# cpuConnectionBoard.net
KiCad netlist of a schematic drawn in EAGLE
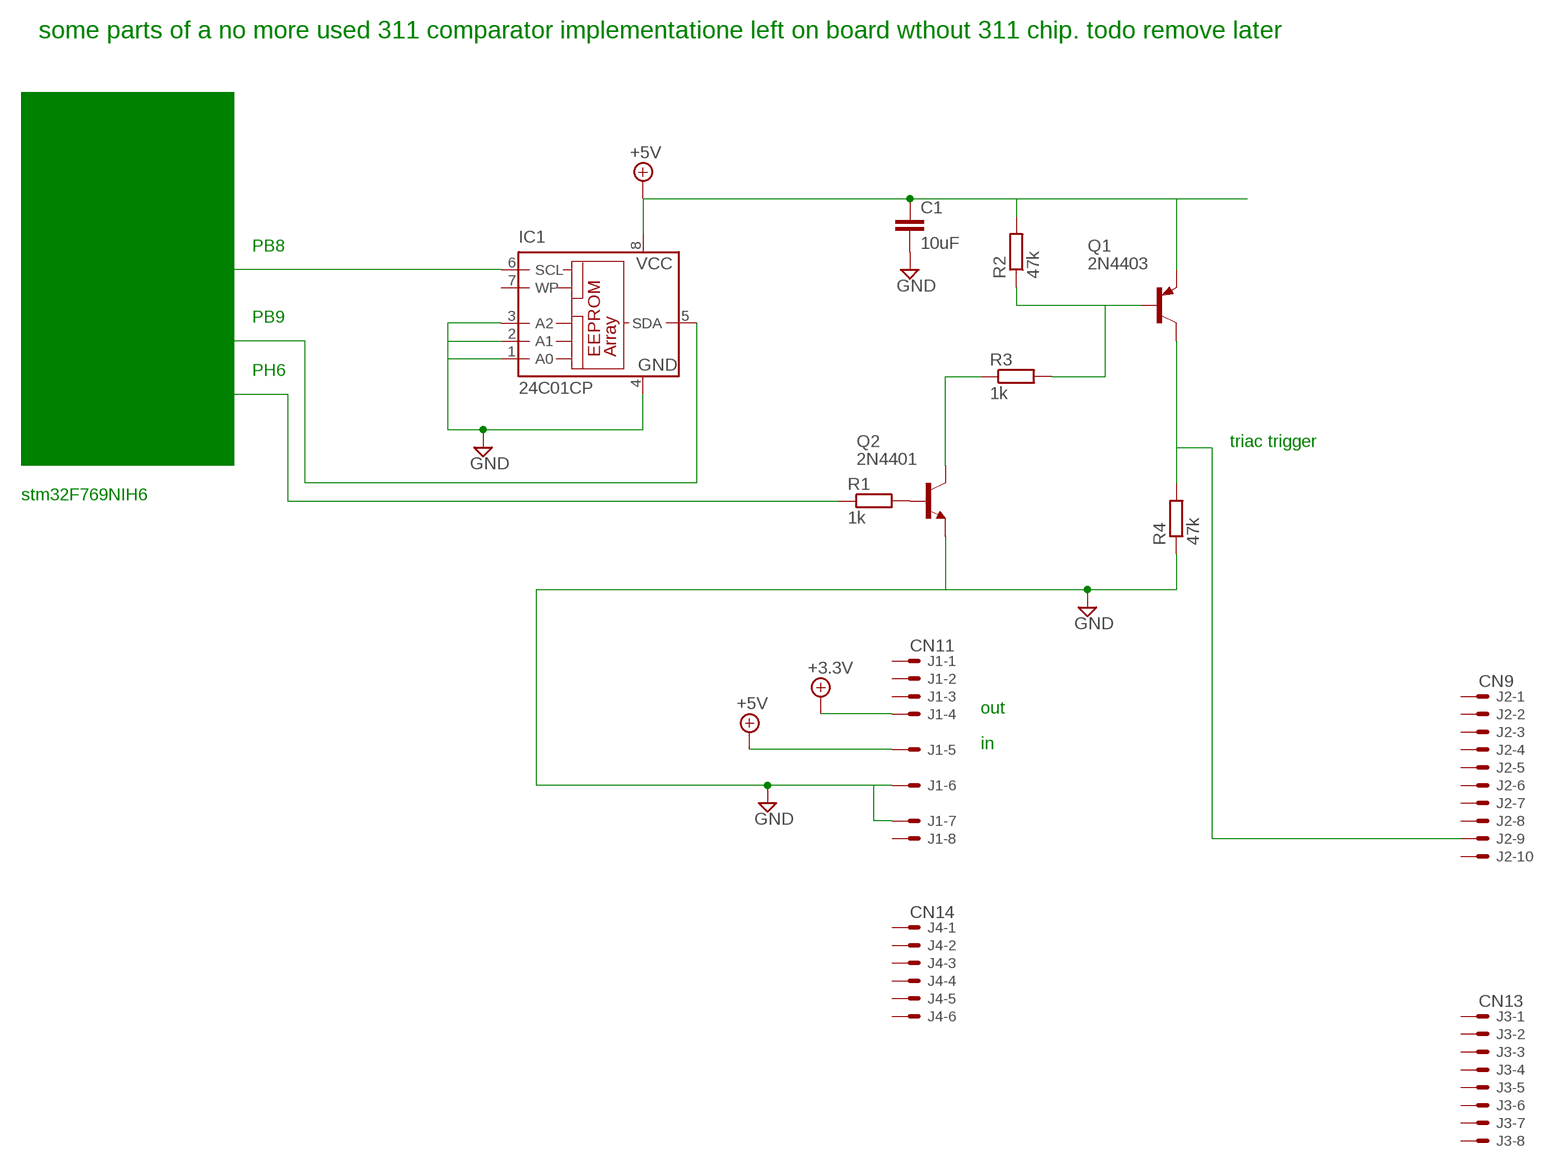
[diagram p0: schematic, sheet 1]

(export (version "E")
  (design (tool "Eeschema 10.0.6"))
  (components
    (comp (ref "C1")
      (value "10uF")
      (footprint "eagle-import:C050-030X075")
      (libsource (lib "eagle-import") (part "C-EU050-030X075"))
    )
    (comp (ref "IC1")
      (value "24C01CP")
      (footprint "eagle-import:DIL8")
      (fields (field (name "MF") "MICROCHIP") (field (name "MPN") "24C01C/P"))
      (libsource (lib "eagle-import") (part "24CP01C"))
    )
    (comp (ref "J1")
      (value "CN11")
      (footprint "eagle-import:XF2E-0815-1")
      (fields (field (name "MPN") "XF2E-0815-1"))
      (libsource (lib "eagle-import") (part "XF2-08?15-1E"))
    )
    (comp (ref "J2")
      (value "CN9")
      (footprint "eagle-import:XF2E-1015-1")
      (fields (field (name "MPN") "XF2E-1015-1"))
      (libsource (lib "eagle-import") (part "XF2-10?15-1E"))
    )
    (comp (ref "J3")
      (value "CN13")
      (footprint "eagle-import:XF2E-0815-1")
      (fields (field (name "MPN") "XF2E-0815-1"))
      (libsource (lib "eagle-import") (part "XF2-08?15-1E"))
    )
    (comp (ref "J4")
      (value "CN14")
      (footprint "eagle-import:XF2E-0815-1")
      (fields (field (name "MPN") "XF2E-0815-1"))
      (libsource (lib "eagle-import") (part "XF2-08?15-1E"))
    )
    (comp (ref "Q1")
      (value "2N4403")
      (footprint "eagle-import:TO3")
      (libsource (lib "eagle-import") (part "2N4902"))
    )
    (comp (ref "Q2")
      (value "2N4401")
      (footprint "eagle-import:TO92")
      (libsource (lib "eagle-import") (part "2N4416"))
    )
    (comp (ref "R1")
      (value "1k")
      (footprint "eagle-import:0309_12")
      (libsource (lib "eagle-import") (part "R-EU_0309/12"))
    )
    (comp (ref "R2")
      (value "47k")
      (footprint "eagle-import:0309_12")
      (libsource (lib "eagle-import") (part "R-EU_0309/12"))
    )
    (comp (ref "R3")
      (value "1k")
      (footprint "eagle-import:0309_12")
      (libsource (lib "eagle-import") (part "R-EU_0309/12"))
    )
    (comp (ref "R4")
      (value "47k")
      (footprint "eagle-import:0309_12")
      (libsource (lib "eagle-import") (part "R-EU_0309/12"))
    )
  )
  (nets
    (net (code "1") (name "+3.3V") (class "Default")
      (node (ref "C1") (pin "1") (pinfunction "1_1") (pintype "passive"))
      (node (ref "IC1") (pin "8") (pinfunction "VCC_8") (pintype "power_in"))
      (node (ref "J1") (pin "4") (pinfunction "MS_4") (pintype "passive"))
      (node (ref "J1") (pin "5") (pinfunction "MS_5") (pintype "passive"))
      (node (ref "Q1") (pin "E") (pinfunction "E_E") (pintype "passive"))
      (node (ref "R2") (pin "2") (pinfunction "2_2") (pintype "passive"))
    )
    (net (code "2") (name "GND") (class "Default")
      (node (ref "C1") (pin "2") (pinfunction "2_2") (pintype "passive"))
      (node (ref "IC1") (pin "1") (pinfunction "A0_1") (pintype "input"))
      (node (ref "IC1") (pin "2") (pinfunction "A1_2") (pintype "input"))
      (node (ref "IC1") (pin "3") (pinfunction "A2_3") (pintype "input"))
      (node (ref "IC1") (pin "4") (pinfunction "GND_4") (pintype "power_in"))
      (node (ref "J1") (pin "6") (pinfunction "MS_6") (pintype "passive"))
      (node (ref "J1") (pin "7") (pinfunction "MS_7") (pintype "passive"))
      (node (ref "Q2") (pin "3") (pinfunction "E_3") (pintype "passive"))
      (node (ref "R4") (pin "1") (pinfunction "1_1") (pintype "passive"))
    )
    (net (code "3") (name "Net-(J2J-MS)") (class "Default")
      (node (ref "J2") (pin "9") (pinfunction "MS_9") (pintype "passive"))
      (node (ref "Q1") (pin "C") (pinfunction "C_C") (pintype "passive"))
      (node (ref "Q1") (pin "C/") (pinfunction "C_C/") (pintype "passive"))
      (node (ref "R4") (pin "2") (pinfunction "2_2") (pintype "passive"))
    )
    (net (code "4") (name "Net-(Q1-PadB)") (class "Default")
      (node (ref "Q1") (pin "B") (pinfunction "B_B") (pintype "passive"))
      (node (ref "R2") (pin "1") (pinfunction "1_1") (pintype "passive"))
      (node (ref "R3") (pin "2") (pinfunction "2_2") (pintype "passive"))
    )
    (net (code "5") (name "Net-(Q2-B)") (class "Default")
      (node (ref "Q2") (pin "2") (pinfunction "B_2") (pintype "passive"))
      (node (ref "R1") (pin "2") (pinfunction "2_2") (pintype "passive"))
    )
    (net (code "6") (name "Net-(Q2-C)") (class "Default")
      (node (ref "Q2") (pin "1") (pinfunction "C_1") (pintype "passive"))
      (node (ref "R3") (pin "1") (pinfunction "1_1") (pintype "passive"))
    )
    (net (code "7") (name "unconnected-(IC1-SCL-Pad6)") (class "Default")
      (node (ref "IC1") (pin "6") (pinfunction "SCL_6") (pintype "input"))
    )
    (net (code "8") (name "unconnected-(IC1-SDA-Pad5)") (class "Default")
      (node (ref "IC1") (pin "5") (pinfunction "SDA_5") (pintype "bidirectional"))
    )
    (net (code "9") (name "unconnected-(IC1-WP-Pad7)") (class "Default")
      (node (ref "IC1") (pin "7") (pinfunction "WP_7") (pintype "input"))
    )
    (net (code "10") (name "unconnected-(J1A-MSV-Pad1)") (class "Default")
      (node (ref "J1") (pin "1") (pinfunction "MSV_1") (pintype "passive"))
    )
    (net (code "11") (name "unconnected-(J1B-MS-Pad2)") (class "Default")
      (node (ref "J1") (pin "2") (pinfunction "MS_2") (pintype "passive"))
    )
    (net (code "12") (name "unconnected-(J1C-MS-Pad3)") (class "Default")
      (node (ref "J1") (pin "3") (pinfunction "MS_3") (pintype "passive"))
    )
    (net (code "13") (name "unconnected-(J1H-MS-Pad8)") (class "Default")
      (node (ref "J1") (pin "8") (pinfunction "MS_8") (pintype "passive"))
    )
    (net (code "14") (name "unconnected-(J2A-MSV-Pad1)") (class "Default")
      (node (ref "J2") (pin "1") (pinfunction "MSV_1") (pintype "passive"))
    )
    (net (code "15") (name "unconnected-(J2B-MS-Pad10)") (class "Default")
      (node (ref "J2") (pin "10") (pinfunction "MS_10") (pintype "passive"))
    )
    (net (code "16") (name "unconnected-(J2C-MS-Pad2)") (class "Default")
      (node (ref "J2") (pin "2") (pinfunction "MS_2") (pintype "passive"))
    )
    (net (code "17") (name "unconnected-(J2D-MS-Pad3)") (class "Default")
      (node (ref "J2") (pin "3") (pinfunction "MS_3") (pintype "passive"))
    )
    (net (code "18") (name "unconnected-(J2E-MS-Pad4)") (class "Default")
      (node (ref "J2") (pin "4") (pinfunction "MS_4") (pintype "passive"))
    )
    (net (code "19") (name "unconnected-(J2F-MS-Pad5)") (class "Default")
      (node (ref "J2") (pin "5") (pinfunction "MS_5") (pintype "passive"))
    )
    (net (code "20") (name "unconnected-(J2G-MS-Pad6)") (class "Default")
      (node (ref "J2") (pin "6") (pinfunction "MS_6") (pintype "passive"))
    )
    (net (code "21") (name "unconnected-(J2H-MS-Pad7)") (class "Default")
      (node (ref "J2") (pin "7") (pinfunction "MS_7") (pintype "passive"))
    )
    (net (code "22") (name "unconnected-(J2I-MS-Pad8)") (class "Default")
      (node (ref "J2") (pin "8") (pinfunction "MS_8") (pintype "passive"))
    )
    (net (code "23") (name "unconnected-(J3A-MSV-Pad1)") (class "Default")
      (node (ref "J3") (pin "1") (pinfunction "MSV_1") (pintype "passive"))
    )
    (net (code "24") (name "unconnected-(J3B-MS-Pad2)") (class "Default")
      (node (ref "J3") (pin "2") (pinfunction "MS_2") (pintype "passive"))
    )
    (net (code "25") (name "unconnected-(J3C-MS-Pad3)") (class "Default")
      (node (ref "J3") (pin "3") (pinfunction "MS_3") (pintype "passive"))
    )
    (net (code "26") (name "unconnected-(J3D-MS-Pad4)") (class "Default")
      (node (ref "J3") (pin "4") (pinfunction "MS_4") (pintype "passive"))
    )
    (net (code "27") (name "unconnected-(J3E-MS-Pad5)") (class "Default")
      (node (ref "J3") (pin "5") (pinfunction "MS_5") (pintype "passive"))
    )
    (net (code "28") (name "unconnected-(J3F-MS-Pad6)") (class "Default")
      (node (ref "J3") (pin "6") (pinfunction "MS_6") (pintype "passive"))
    )
    (net (code "29") (name "unconnected-(J3G-MS-Pad7)") (class "Default")
      (node (ref "J3") (pin "7") (pinfunction "MS_7") (pintype "passive"))
    )
    (net (code "30") (name "unconnected-(J3H-MS-Pad8)") (class "Default")
      (node (ref "J3") (pin "8") (pinfunction "MS_8") (pintype "passive"))
    )
    (net (code "31") (name "unconnected-(J4A-MSV-Pad1)") (class "Default")
      (node (ref "J4") (pin "1") (pinfunction "MSV_1") (pintype "passive"))
    )
    (net (code "32") (name "unconnected-(J4B-MS-Pad2)") (class "Default")
      (node (ref "J4") (pin "2") (pinfunction "MS_2") (pintype "passive"))
    )
    (net (code "33") (name "unconnected-(J4C-MS-Pad3)") (class "Default")
      (node (ref "J4") (pin "3") (pinfunction "MS_3") (pintype "passive"))
    )
    (net (code "34") (name "unconnected-(J4D-MS-Pad4)") (class "Default")
      (node (ref "J4") (pin "4") (pinfunction "MS_4") (pintype "passive"))
    )
    (net (code "35") (name "unconnected-(J4E-MS-Pad5)") (class "Default")
      (node (ref "J4") (pin "5") (pinfunction "MS_5") (pintype "passive"))
    )
    (net (code "36") (name "unconnected-(J4F-MS-Pad6)") (class "Default")
      (node (ref "J4") (pin "6") (pinfunction "MS_6") (pintype "passive"))
    )
    (net (code "37") (name "unconnected-(R1-Pad1)") (class "Default")
      (node (ref "R1") (pin "1") (pinfunction "1_1") (pintype "passive"))
    )
  )
)
